# Projek1.net
KiCad netlist of a schematic drawn in EAGLE
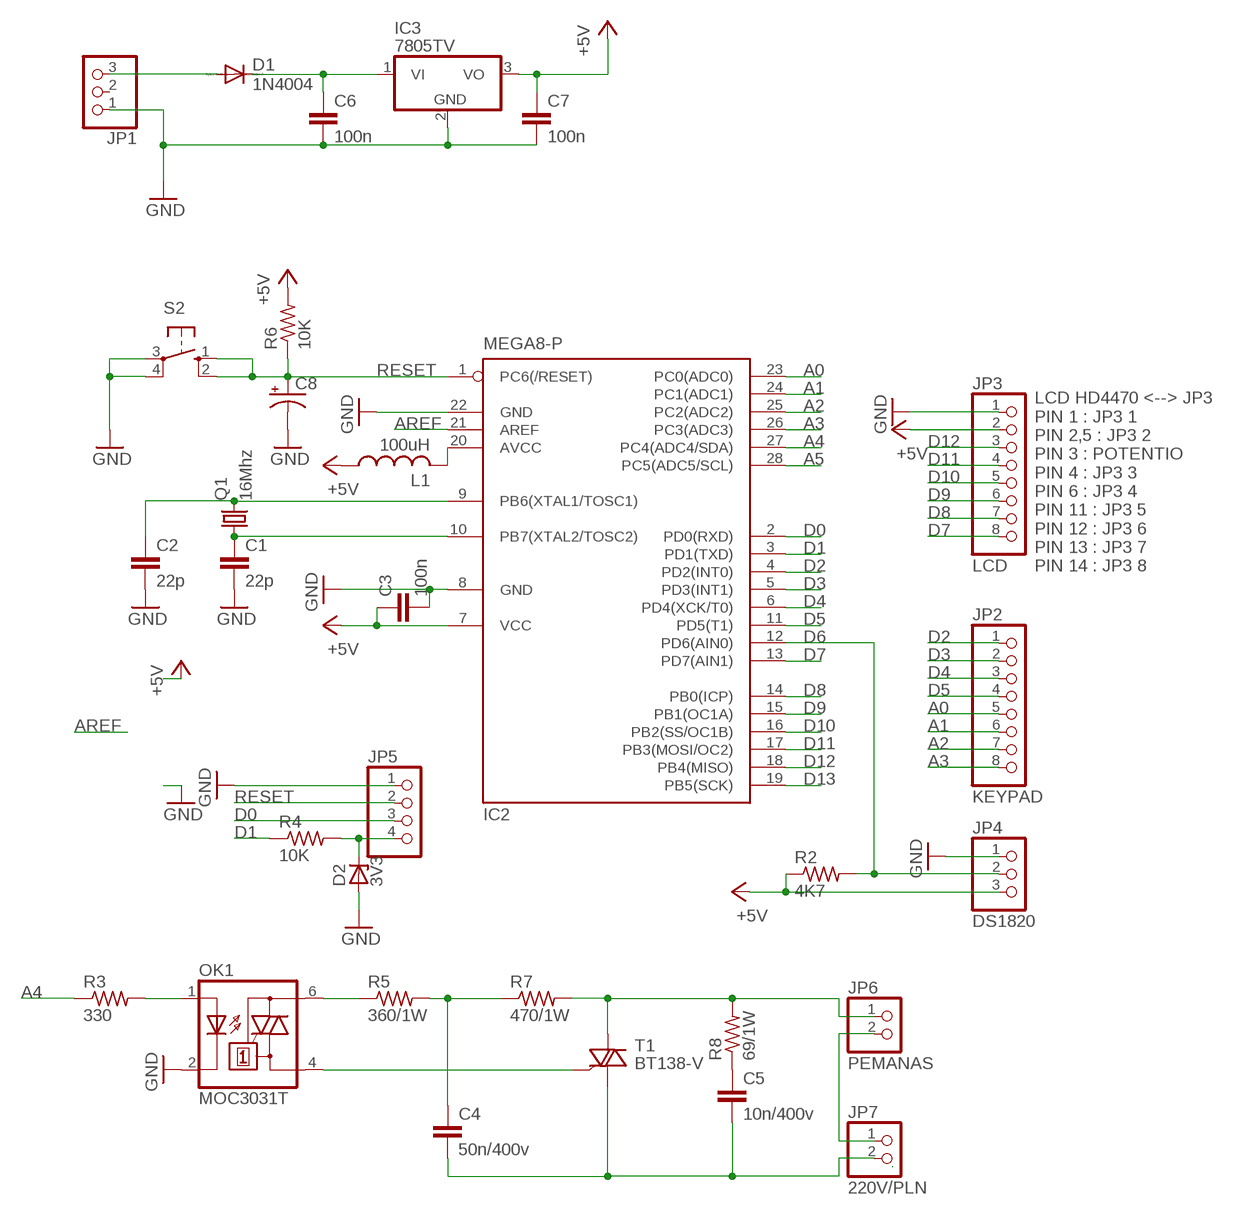
[diagram p0: schematic, sheet 1]

(export (version "E")
  (design (tool "Eeschema 10.0.6"))
  (components
    (comp (ref "C1")
      (value "22p")
      (footprint "eagle-import:C025-025X050")
      (libsource (lib "eagle-import") (part "C-EU025-025X050"))
    )
    (comp (ref "C2")
      (value "22p")
      (footprint "eagle-import:C025-025X050")
      (libsource (lib "eagle-import") (part "C-EU025-025X050"))
    )
    (comp (ref "C3")
      (value "100n")
      (footprint "eagle-import:C050-025X075")
      (libsource (lib "eagle-import") (part "C-EU050-025X075"))
    )
    (comp (ref "C4")
      (value "50n/400v")
      (footprint "eagle-import:C150-064X183")
      (libsource (lib "eagle-import") (part "C-EU150-064X183"))
    )
    (comp (ref "C5")
      (value "10n/400v")
      (footprint "eagle-import:C150-064X183")
      (libsource (lib "eagle-import") (part "C-EU150-064X183"))
    )
    (comp (ref "C6")
      (value "100n")
      (footprint "eagle-import:C050-025X075")
      (libsource (lib "eagle-import") (part "C-EU050-025X075"))
    )
    (comp (ref "C7")
      (value "100n")
      (footprint "eagle-import:C050-025X075")
      (libsource (lib "eagle-import") (part "C-EU050-025X075"))
    )
    (comp (ref "C8")
      (value "CPOL-USE2-5")
      (footprint "eagle-import:E2-5")
      (libsource (lib "eagle-import") (part "CPOL-USE2-5"))
    )
    (comp (ref "D1")
      (value "1N4004")
      (footprint "eagle-import:DO41-10")
      (libsource (lib "eagle-import") (part "1N4004"))
    )
    (comp (ref "D2")
      (value "3V3")
      (footprint "eagle-import:DO35Z10")
      (libsource (lib "eagle-import") (part "ZENER-DIODEDO35Z10"))
    )
    (comp (ref "IC2")
      (value "MEGA8-P")
      (footprint "eagle-import:DIL28-3")
      (libsource (lib "eagle-import") (part "MEGA8-P"))
    )
    (comp (ref "IC3")
      (value "7805TV")
      (footprint "eagle-import:TO220V")
      (libsource (lib "eagle-import") (part "78TV05"))
    )
    (comp (ref "JP1")
      (value "PINHD-1X3")
      (footprint "eagle-import:1X03")
      (libsource (lib "eagle-import") (part "PINHD-1X3"))
    )
    (comp (ref "JP2")
      (value "KEYPAD")
      (footprint "eagle-import:1X08")
      (libsource (lib "eagle-import") (part "PINHD-1X8"))
    )
    (comp (ref "JP3")
      (value "LCD")
      (footprint "eagle-import:1X08")
      (libsource (lib "eagle-import") (part "PINHD-1X8"))
    )
    (comp (ref "JP4")
      (value "DS1820")
      (footprint "eagle-import:1X03")
      (libsource (lib "eagle-import") (part "PINHD-1X3"))
    )
    (comp (ref "JP5")
      (value "PINHD-1X4")
      (footprint "eagle-import:1X04")
      (libsource (lib "eagle-import") (part "PINHD-1X4"))
    )
    (comp (ref "JP6")
      (value "PEMANAS")
      (footprint "eagle-import:1X02")
      (libsource (lib "eagle-import") (part "PINHD-1X2"))
    )
    (comp (ref "JP7")
      (value "220V/PLN")
      (footprint "eagle-import:1X02")
      (libsource (lib "eagle-import") (part "PINHD-1X2"))
    )
    (comp (ref "L1")
      (value "100uH")
      (footprint "eagle-import:0207_10")
      (libsource (lib "eagle-import") (part "L-US0207/10"))
    )
    (comp (ref "OK1")
      (value "MOC3031T")
      (footprint "eagle-import:DIL06B")
      (libsource (lib "eagle-import") (part "MOC30T31"))
    )
    (comp (ref "Q1")
      (value "16Mhz")
      (footprint "eagle-import:HC49U70")
      (libsource (lib "eagle-import") (part "CRYSTALHC49U70"))
    )
    (comp (ref "R2")
      (value "4K7")
      (footprint "eagle-import:0309_10")
      (libsource (lib "eagle-import") (part "R-US_0309/10"))
    )
    (comp (ref "R3")
      (value "330")
      (footprint "eagle-import:0309_10")
      (libsource (lib "eagle-import") (part "R-US_0309/10"))
    )
    (comp (ref "R4")
      (value "10K")
      (footprint "eagle-import:0309_10")
      (libsource (lib "eagle-import") (part "R-US_0309/10"))
    )
    (comp (ref "R5")
      (value "360/1W")
      (footprint "eagle-import:0414_15")
      (libsource (lib "eagle-import") (part "R-US_0414/15"))
    )
    (comp (ref "R6")
      (value "10K")
      (footprint "eagle-import:0309_10")
      (libsource (lib "eagle-import") (part "R-US_0309/10"))
    )
    (comp (ref "R7")
      (value "470/1W")
      (footprint "eagle-import:0414_15")
      (libsource (lib "eagle-import") (part "R-US_0414/15"))
    )
    (comp (ref "R8")
      (value "69/1W")
      (footprint "eagle-import:0414_15")
      (libsource (lib "eagle-import") (part "R-US_0414/15"))
    )
    (comp (ref "S2")
      (value "10-XX")
      (footprint "eagle-import:B3F-10XX")
      (fields (field (name "MPN") "B3F-1000"))
      (libsource (lib "eagle-import") (part "10-XX"))
    )
    (comp (ref "T1")
      (value "BT138-V")
      (footprint "eagle-import:TO220BV")
      (libsource (lib "eagle-import") (part "BT138-V"))
    )
  )
  (nets
    (net (code "1") (name "+5V") (class "Default")
      (node (ref "C3") (pin "1") (pinfunction "1_1") (pintype "passive"))
      (node (ref "C7") (pin "1") (pinfunction "1_1") (pintype "passive"))
      (node (ref "IC2") (pin "7") (pinfunction "VCC_7") (pintype "power_in"))
      (node (ref "IC3") (pin "3") (pinfunction "VO_3") (pintype "passive"))
      (node (ref "JP3") (pin "2") (pinfunction "2_2") (pintype "passive"))
      (node (ref "JP4") (pin "3") (pinfunction "3_3") (pintype "passive"))
      (node (ref "L1") (pin "1") (pinfunction "1_1") (pintype "passive"))
      (node (ref "R2") (pin "1") (pinfunction "1_1") (pintype "passive"))
      (node (ref "R6") (pin "2") (pinfunction "2_2") (pintype "passive"))
    )
    (net (code "2") (name "/A0") (class "Default")
      (node (ref "IC2") (pin "23") (pinfunction "PC0(ADC0)_23") (pintype "bidirectional"))
      (node (ref "JP2") (pin "5") (pinfunction "5_5") (pintype "passive"))
    )
    (net (code "3") (name "/A1") (class "Default")
      (node (ref "IC2") (pin "24") (pinfunction "PC1(ADC1)_24") (pintype "bidirectional"))
      (node (ref "JP2") (pin "6") (pinfunction "6_6") (pintype "passive"))
    )
    (net (code "4") (name "/A2") (class "Default")
      (node (ref "IC2") (pin "25") (pinfunction "PC2(ADC2)_25") (pintype "bidirectional"))
      (node (ref "JP2") (pin "7") (pinfunction "7_7") (pintype "passive"))
    )
    (net (code "5") (name "/A3") (class "Default")
      (node (ref "IC2") (pin "26") (pinfunction "PC3(ADC3)_26") (pintype "bidirectional"))
      (node (ref "JP2") (pin "8") (pinfunction "8_8") (pintype "passive"))
    )
    (net (code "6") (name "/A4") (class "Default")
      (node (ref "IC2") (pin "27") (pinfunction "PC4(ADC4/SDA)_27") (pintype "bidirectional"))
      (node (ref "R3") (pin "1") (pinfunction "1_1") (pintype "passive"))
    )
    (net (code "7") (name "/A5") (class "Default")
      (node (ref "IC2") (pin "28") (pinfunction "PC5(ADC5/SCL)_28") (pintype "bidirectional"))
    )
    (net (code "8") (name "/AREF") (class "Default")
      (node (ref "IC2") (pin "21") (pinfunction "AREF_21") (pintype "passive"))
    )
    (net (code "9") (name "/D0") (class "Default")
      (node (ref "IC2") (pin "2") (pinfunction "PD0(RXD)_2") (pintype "bidirectional"))
      (node (ref "JP5") (pin "3") (pinfunction "3_3") (pintype "passive"))
    )
    (net (code "10") (name "/D1") (class "Default")
      (node (ref "IC2") (pin "3") (pinfunction "PD1(TXD)_3") (pintype "bidirectional"))
      (node (ref "R4") (pin "1") (pinfunction "1_1") (pintype "passive"))
    )
    (net (code "11") (name "/D2") (class "Default")
      (node (ref "IC2") (pin "4") (pinfunction "PD2(INT0)_4") (pintype "bidirectional"))
      (node (ref "JP2") (pin "1") (pinfunction "1_1") (pintype "passive"))
    )
    (net (code "12") (name "/D3") (class "Default")
      (node (ref "IC2") (pin "5") (pinfunction "PD3(INT1)_5") (pintype "bidirectional"))
      (node (ref "JP2") (pin "2") (pinfunction "2_2") (pintype "passive"))
    )
    (net (code "13") (name "/D4") (class "Default")
      (node (ref "IC2") (pin "6") (pinfunction "PD4(XCK/T0)_6") (pintype "bidirectional"))
      (node (ref "JP2") (pin "3") (pinfunction "3_3") (pintype "passive"))
    )
    (net (code "14") (name "/D5") (class "Default")
      (node (ref "IC2") (pin "11") (pinfunction "PD5(T1)_11") (pintype "bidirectional"))
      (node (ref "JP2") (pin "4") (pinfunction "4_4") (pintype "passive"))
    )
    (net (code "15") (name "/D6") (class "Default")
      (node (ref "IC2") (pin "12") (pinfunction "PD6(AIN0)_12") (pintype "bidirectional"))
      (node (ref "JP4") (pin "2") (pinfunction "2_2") (pintype "passive"))
      (node (ref "R2") (pin "2") (pinfunction "2_2") (pintype "passive"))
    )
    (net (code "16") (name "/D7") (class "Default")
      (node (ref "IC2") (pin "13") (pinfunction "PD7(AIN1)_13") (pintype "bidirectional"))
      (node (ref "JP3") (pin "8") (pinfunction "8_8") (pintype "passive"))
    )
    (net (code "17") (name "/D8") (class "Default")
      (node (ref "IC2") (pin "14") (pinfunction "PB0(ICP)_14") (pintype "bidirectional"))
      (node (ref "JP3") (pin "7") (pinfunction "7_7") (pintype "passive"))
    )
    (net (code "18") (name "/D9") (class "Default")
      (node (ref "IC2") (pin "15") (pinfunction "PB1(OC1A)_15") (pintype "bidirectional"))
      (node (ref "JP3") (pin "6") (pinfunction "6_6") (pintype "passive"))
    )
    (net (code "19") (name "/D10") (class "Default")
      (node (ref "IC2") (pin "16") (pinfunction "PB2(SS/OC1B)_16") (pintype "bidirectional"))
      (node (ref "JP3") (pin "5") (pinfunction "5_5") (pintype "passive"))
    )
    (net (code "20") (name "/D11") (class "Default")
      (node (ref "IC2") (pin "17") (pinfunction "PB3(MOSI/OC2)_17") (pintype "bidirectional"))
      (node (ref "JP3") (pin "4") (pinfunction "4_4") (pintype "passive"))
    )
    (net (code "21") (name "/D12") (class "Default")
      (node (ref "IC2") (pin "18") (pinfunction "PB4(MISO)_18") (pintype "bidirectional"))
      (node (ref "JP3") (pin "3") (pinfunction "3_3") (pintype "passive"))
    )
    (net (code "22") (name "/D13") (class "Default")
      (node (ref "IC2") (pin "19") (pinfunction "PB5(SCK)_19") (pintype "bidirectional"))
    )
    (net (code "23") (name "/RESET") (class "Default")
      (node (ref "C8") (pin "+") (pinfunction "+_+") (pintype "passive"))
      (node (ref "IC2") (pin "1") (pinfunction "PC6(/RESET)_1") (pintype "bidirectional"))
      (node (ref "JP5") (pin "2") (pinfunction "2_2") (pintype "passive"))
      (node (ref "R6") (pin "1") (pinfunction "1_1") (pintype "passive"))
      (node (ref "S2") (pin "1") (pinfunction "S_1") (pintype "passive"))
      (node (ref "S2") (pin "2") (pinfunction "S1_2") (pintype "passive"))
    )
    (net (code "24") (name "GND") (class "Default")
      (node (ref "C1") (pin "2") (pinfunction "2_2") (pintype "passive"))
      (node (ref "C2") (pin "2") (pinfunction "2_2") (pintype "passive"))
      (node (ref "C3") (pin "2") (pinfunction "2_2") (pintype "passive"))
      (node (ref "C6") (pin "2") (pinfunction "2_2") (pintype "passive"))
      (node (ref "C7") (pin "2") (pinfunction "2_2") (pintype "passive"))
      (node (ref "C8") (pin "-") (pinfunction "-_-") (pintype "passive"))
      (node (ref "D2") (pin "A") (pinfunction "A_A") (pintype "passive"))
      (node (ref "IC2") (pin "22") (pinfunction "GND_22") (pintype "power_in"))
      (node (ref "IC2") (pin "8") (pinfunction "GND_8") (pintype "power_in"))
      (node (ref "IC3") (pin "2") (pinfunction "GND_2") (pintype "passive"))
      (node (ref "JP1") (pin "1") (pinfunction "1_1") (pintype "passive"))
      (node (ref "JP3") (pin "1") (pinfunction "1_1") (pintype "passive"))
      (node (ref "JP4") (pin "1") (pinfunction "1_1") (pintype "passive"))
      (node (ref "JP5") (pin "1") (pinfunction "1_1") (pintype "passive"))
      (node (ref "OK1") (pin "2") (pinfunction "C_2") (pintype "passive"))
      (node (ref "S2") (pin "3") (pinfunction "P_3") (pintype "passive"))
      (node (ref "S2") (pin "4") (pinfunction "P1_4") (pintype "passive"))
    )
    (net (code "25") (name "Net-(C4-Pad1)") (class "Default")
      (node (ref "C4") (pin "1") (pinfunction "1_1") (pintype "passive"))
      (node (ref "R5") (pin "2") (pinfunction "2_2") (pintype "passive"))
      (node (ref "R7") (pin "1") (pinfunction "1_1") (pintype "passive"))
    )
    (net (code "26") (name "Net-(C5-Pad1)") (class "Default")
      (node (ref "C5") (pin "1") (pinfunction "1_1") (pintype "passive"))
      (node (ref "R8") (pin "1") (pinfunction "1_1") (pintype "passive"))
    )
    (net (code "27") (name "Net-(D1-PadA)") (class "Default")
      (node (ref "D1") (pin "A") (pinfunction "A_A") (pintype "passive"))
      (node (ref "JP1") (pin "3") (pinfunction "3_3") (pintype "passive"))
    )
    (net (code "28") (name "Net-(D2-PadC)") (class "Default")
      (node (ref "D2") (pin "C") (pinfunction "C_C") (pintype "passive"))
      (node (ref "JP5") (pin "4") (pinfunction "4_4") (pintype "passive"))
      (node (ref "R4") (pin "2") (pinfunction "2_2") (pintype "passive"))
    )
    (net (code "29") (name "Net-(IC2-AVCC)") (class "Default")
      (node (ref "IC2") (pin "20") (pinfunction "AVCC_20") (pintype "power_in"))
      (node (ref "L1") (pin "2") (pinfunction "2_2") (pintype "passive"))
    )
    (net (code "30") (name "Net-(IC2-PB6(XTAL1{slash}TOSC1))") (class "Default")
      (node (ref "C2") (pin "1") (pinfunction "1_1") (pintype "passive"))
      (node (ref "IC2") (pin "9") (pinfunction "PB6(XTAL1/TOSC1)_9") (pintype "bidirectional"))
      (node (ref "Q1") (pin "2") (pinfunction "2_2") (pintype "passive"))
    )
    (net (code "31") (name "Net-(IC2-PB7(XTAL2{slash}TOSC2))") (class "Default")
      (node (ref "C1") (pin "1") (pinfunction "1_1") (pintype "passive"))
      (node (ref "IC2") (pin "10") (pinfunction "PB7(XTAL2/TOSC2)_10") (pintype "bidirectional"))
      (node (ref "Q1") (pin "1") (pinfunction "1_1") (pintype "passive"))
    )
    (net (code "32") (name "Net-(IC3-VI)") (class "Default")
      (node (ref "C6") (pin "1") (pinfunction "1_1") (pintype "passive"))
      (node (ref "D1") (pin "C") (pinfunction "C_C") (pintype "passive"))
      (node (ref "IC3") (pin "1") (pinfunction "VI_1") (pintype "input"))
    )
    (net (code "33") (name "Net-(JP6-Pad2)") (class "Default")
      (node (ref "JP6") (pin "2") (pinfunction "2_2") (pintype "passive"))
      (node (ref "JP7") (pin "1") (pinfunction "1_1") (pintype "passive"))
    )
    (net (code "34") (name "Net-(OK1-A)") (class "Default")
      (node (ref "OK1") (pin "1") (pinfunction "A_1") (pintype "passive"))
      (node (ref "R3") (pin "2") (pinfunction "2_2") (pintype "passive"))
    )
    (net (code "35") (name "Net-(OK1-A1)") (class "Default")
      (node (ref "OK1") (pin "4") (pinfunction "A1_4") (pintype "passive"))
      (node (ref "T1") (pin "G") (pinfunction "G_G") (pintype "passive"))
    )
    (net (code "36") (name "Net-(OK1-A2)") (class "Default")
      (node (ref "OK1") (pin "6") (pinfunction "A2_6") (pintype "passive"))
      (node (ref "R5") (pin "1") (pinfunction "1_1") (pintype "passive"))
    )
    (net (code "37") (name "Net-(T1-A1)") (class "Default")
      (node (ref "C4") (pin "2") (pinfunction "2_2") (pintype "passive"))
      (node (ref "C5") (pin "2") (pinfunction "2_2") (pintype "passive"))
      (node (ref "JP7") (pin "2") (pinfunction "2_2") (pintype "passive"))
      (node (ref "T1") (pin "T1") (pinfunction "A1_T1") (pintype "passive"))
    )
    (net (code "38") (name "Net-(T1-A2)") (class "Default")
      (node (ref "JP6") (pin "1") (pinfunction "1_1") (pintype "passive"))
      (node (ref "R7") (pin "2") (pinfunction "2_2") (pintype "passive"))
      (node (ref "R8") (pin "2") (pinfunction "2_2") (pintype "passive"))
      (node (ref "T1") (pin "T2") (pinfunction "A2_T2") (pintype "passive"))
    )
    (net (code "39") (name "unconnected-(JP1-Pad2)") (class "Default")
      (node (ref "JP1") (pin "2") (pinfunction "2_2") (pintype "passive"))
    )
  )
)
